# LowVBoard_2_0.net
KiCad netlist of a schematic drawn in EAGLE
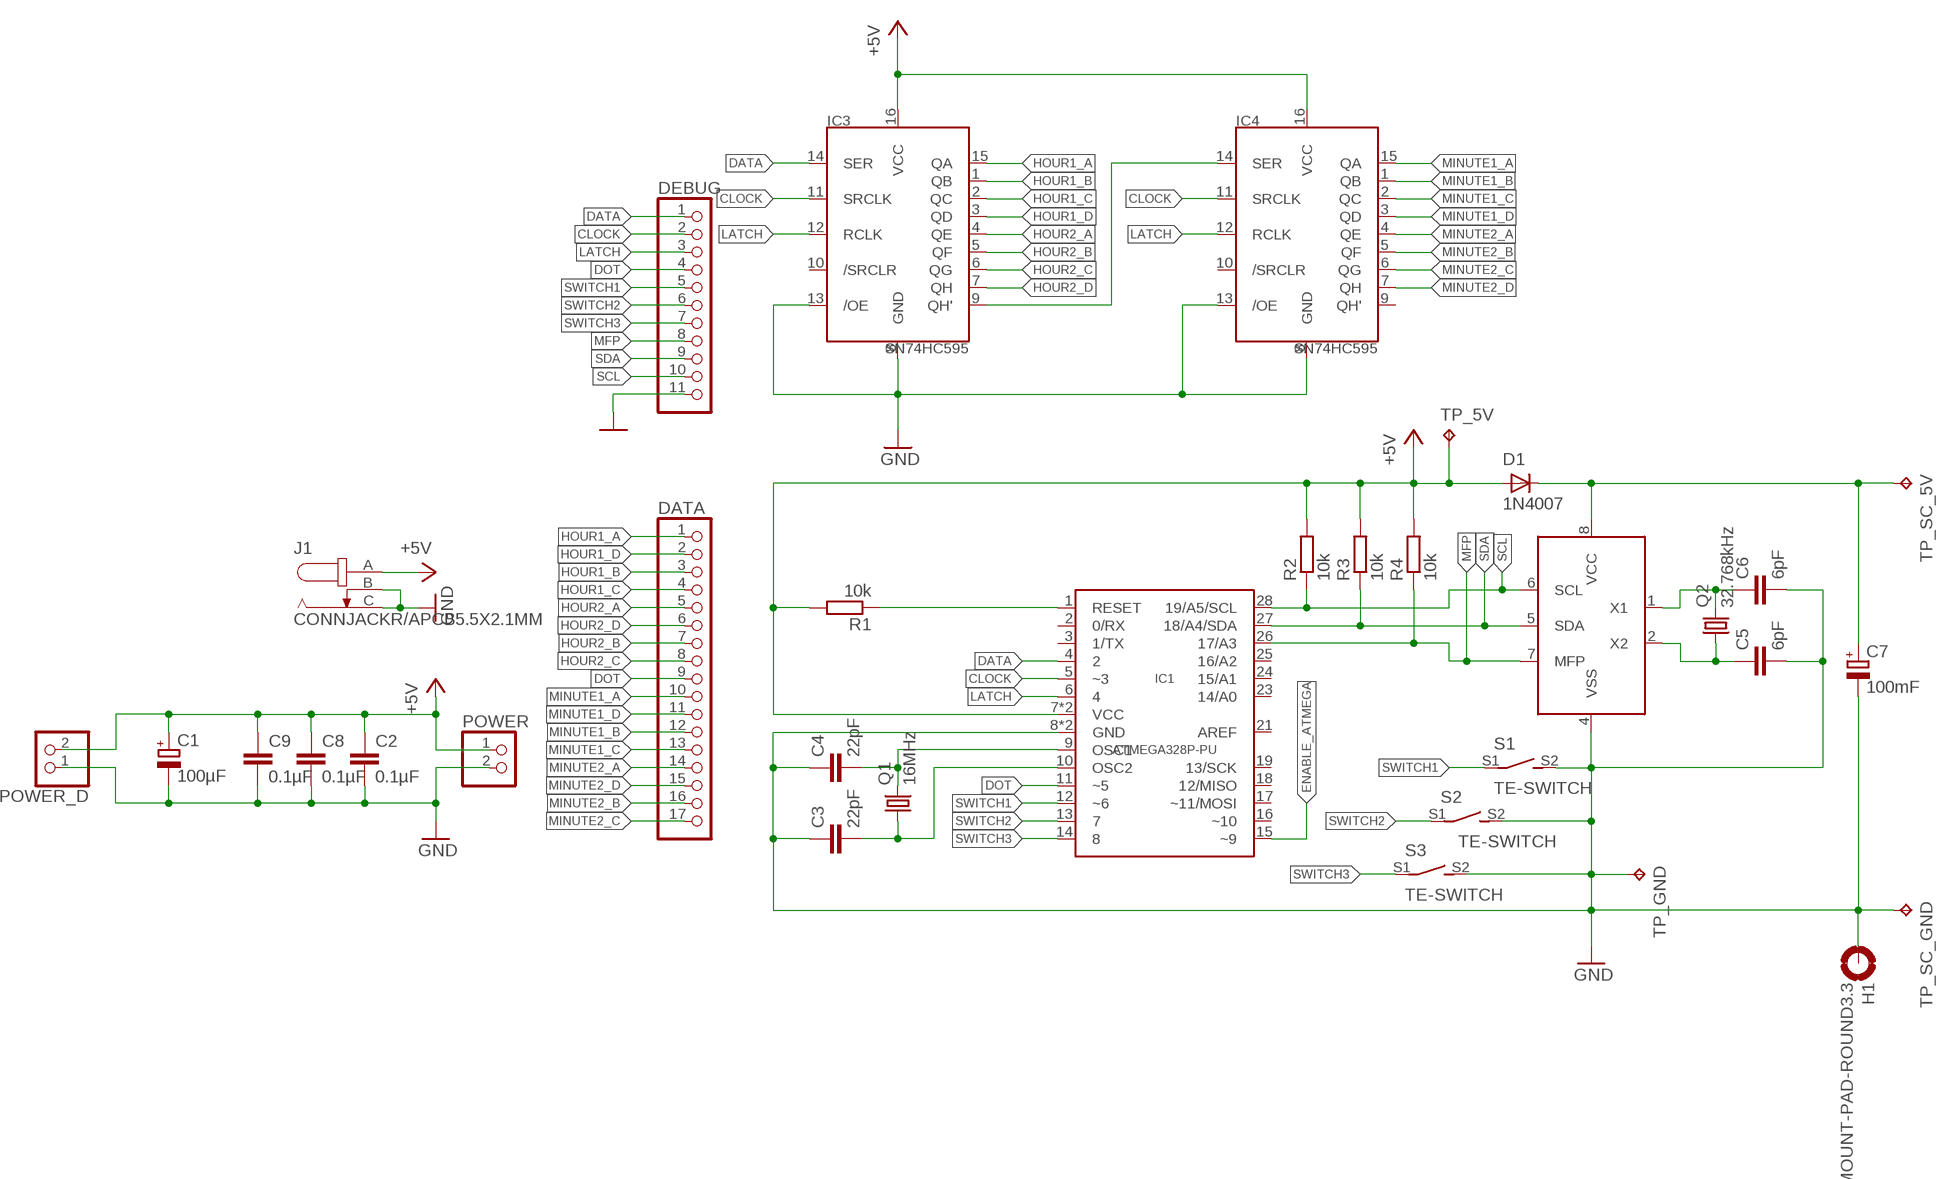
[diagram p0: schematic, sheet 1]

(export (version "E")
  (design (tool "Eeschema 10.0.6"))
  (components
    (comp (ref "C1")
      (value "100µF")
      (footprint "eagle-import:E2-5")
      (libsource (lib "eagle-import") (part "CPOL-EUE2-5"))
    )
    (comp (ref "C2")
      (value "0.1µF")
      (footprint "eagle-import:C025-024X044")
      (libsource (lib "eagle-import") (part "C-EU025-024X044"))
    )
    (comp (ref "C3")
      (value "22pF")
      (footprint "eagle-import:C025-024X044")
      (libsource (lib "eagle-import") (part "C-EU025-024X044"))
    )
    (comp (ref "C4")
      (value "22pF")
      (footprint "eagle-import:C025-024X044")
      (libsource (lib "eagle-import") (part "C-EU025-024X044"))
    )
    (comp (ref "C5")
      (value "6pF")
      (footprint "eagle-import:C025-024X044")
      (libsource (lib "eagle-import") (part "C-EU025-024X044"))
    )
    (comp (ref "C6")
      (value "6pF")
      (footprint "eagle-import:C025-024X044")
      (libsource (lib "eagle-import") (part "C-EU025-024X044"))
    )
    (comp (ref "C7")
      (value "100mF")
      (footprint "eagle-import:SUPERCAP-11.5")
      (libsource (lib "eagle-import") (part "FTW0H104ZF"))
    )
    (comp (ref "C8")
      (value "0.1µF")
      (footprint "eagle-import:C025-024X044")
      (libsource (lib "eagle-import") (part "C-EU025-024X044"))
    )
    (comp (ref "C9")
      (value "0.1µF")
      (footprint "eagle-import:C025-024X044")
      (libsource (lib "eagle-import") (part "C-EU025-024X044"))
    )
    (comp (ref "D1")
      (value "1N4007")
      (footprint "eagle-import:DO41-7.6")
      (libsource (lib "eagle-import") (part "1N4007"))
    )
    (comp (ref "DATA")
      (value "PINHD-1X17")
      (footprint "eagle-import:1X17")
      (libsource (lib "eagle-import") (part "PINHD-1X17"))
    )
    (comp (ref "DEBUG")
      (value "PINHD-1X11/90")
      (footprint "eagle-import:1X11_90")
      (libsource (lib "eagle-import") (part "PINHD-1X11/90"))
    )
    (comp (ref "H1")
      (value "MOUNT-PAD-ROUND3.3")
      (footprint "eagle-import:3,3-PAD")
      (libsource (lib "eagle-import") (part "MOUNT-PAD-ROUND3.3"))
    )
    (comp (ref "IC1")
      (value "ATMEGA328P-PU")
      (footprint "eagle-import:DIP28")
      (libsource (lib "eagle-import") (part "ATMEGA328P-PU"))
    )
    (comp (ref "IC2")
      (value "MCP7940M")
      (footprint "eagle-import:DIL8")
      (libsource (lib "eagle-import") (part "MCP7940M-I/P"))
    )
    (comp (ref "IC3")
      (value "SN74HC595")
      (footprint "eagle-import:DIL16")
      (libsource (lib "eagle-import") (part "SN74HC595"))
    )
    (comp (ref "IC4")
      (value "SN74HC595")
      (footprint "eagle-import:DIL16")
      (libsource (lib "eagle-import") (part "SN74HC595"))
    )
    (comp (ref "J1")
      (value "CONNJACKR/APCB5.5X2.1MM")
      (footprint "eagle-import:CONNJACKR_APCB5.5X2.1MM")
      (libsource (lib "eagle-import") (part "CONNJACKR/APCB5.5X2.1MM"))
    )
    (comp (ref "POWER")
      (value "PINHD-1X2")
      (footprint "eagle-import:1X02")
      (libsource (lib "eagle-import") (part "PINHD-1X2"))
    )
    (comp (ref "POWER_D")
      (value "PINHD-1X2/90")
      (footprint "eagle-import:1X02_90")
      (libsource (lib "eagle-import") (part "PINHD-1X2/90"))
    )
    (comp (ref "Q1")
      (value "16MHz")
      (footprint "eagle-import:HC49_S")
      (libsource (lib "eagle-import") (part "CRYSTALHC49S"))
    )
    (comp (ref "Q2")
      (value "32.768kHz")
      (footprint "eagle-import:CFS-206")
      (libsource (lib "eagle-import") (part "CFS-206"))
    )
    (comp (ref "R1")
      (value "10k")
      (footprint "eagle-import:0207_7")
      (libsource (lib "eagle-import") (part "R-EU_0207/7"))
    )
    (comp (ref "R2")
      (value "10k")
      (footprint "eagle-import:0207_7")
      (libsource (lib "eagle-import") (part "R-EU_0207/7"))
    )
    (comp (ref "R3")
      (value "10k")
      (footprint "eagle-import:0207_7")
      (libsource (lib "eagle-import") (part "R-EU_0207/7"))
    )
    (comp (ref "R4")
      (value "10k")
      (footprint "eagle-import:0207_7")
      (libsource (lib "eagle-import") (part "R-EU_0207/7"))
    )
    (comp (ref "S1")
      (value "TE-SWITCH")
      (footprint "eagle-import:TE-SWITCH")
      (libsource (lib "eagle-import") (part "TE-SWITCH"))
    )
    (comp (ref "S2")
      (value "TE-SWITCH")
      (footprint "eagle-import:TE-SWITCH")
      (libsource (lib "eagle-import") (part "TE-SWITCH"))
    )
    (comp (ref "S3")
      (value "TE-SWITCH")
      (footprint "eagle-import:TE-SWITCH")
      (libsource (lib "eagle-import") (part "TE-SWITCH"))
    )
    (comp (ref "TP_5V")
      (value "TPPAD1-13")
      (footprint "eagle-import:P1-13")
      (libsource (lib "eagle-import") (part "TPPAD1-13"))
    )
    (comp (ref "TP_GND")
      (value "TPPAD1-13")
      (footprint "eagle-import:P1-13")
      (libsource (lib "eagle-import") (part "TPPAD1-13"))
    )
    (comp (ref "TP_SC_5V")
      (value "TPPAD1-13")
      (footprint "eagle-import:P1-13")
      (libsource (lib "eagle-import") (part "TPPAD1-13"))
    )
    (comp (ref "TP_SC_GND")
      (value "TPPAD1-13")
      (footprint "eagle-import:P1-13")
      (libsource (lib "eagle-import") (part "TPPAD1-13"))
    )
  )
  (nets
    (net (code "1") (name "+5V") (class "Default")
      (node (ref "C1") (pin "+") (pinfunction "+_+") (pintype "passive"))
      (node (ref "C2") (pin "1") (pinfunction "1_1") (pintype "passive"))
      (node (ref "C8") (pin "1") (pinfunction "1_1") (pintype "passive"))
      (node (ref "C9") (pin "1") (pinfunction "1_1") (pintype "passive"))
      (node (ref "D1") (pin "A") (pinfunction "A_A") (pintype "passive"))
      (node (ref "IC1") (pin "20") (pinfunction "VCC_20") (pintype "bidirectional"))
      (node (ref "IC1") (pin "7") (pinfunction "VCC_7") (pintype "bidirectional"))
      (node (ref "IC3") (pin "16") (pinfunction "VCC_16") (pintype "bidirectional"))
      (node (ref "IC4") (pin "16") (pinfunction "VCC_16") (pintype "bidirectional"))
      (node (ref "J1") (pin "A") (pinfunction "A_A") (pintype "passive"))
      (node (ref "POWER") (pin "1") (pinfunction "1_1") (pintype "passive"))
      (node (ref "POWER_D") (pin "2") (pinfunction "2_2") (pintype "passive"))
      (node (ref "R1") (pin "2") (pinfunction "2_2") (pintype "passive"))
      (node (ref "R2") (pin "2") (pinfunction "2_2") (pintype "passive"))
      (node (ref "R3") (pin "2") (pinfunction "2_2") (pintype "passive"))
      (node (ref "R4") (pin "2") (pinfunction "2_2") (pintype "passive"))
      (node (ref "TP_5V") (pin "TP") (pinfunction "TP_TP") (pintype "input"))
    )
    (net (code "2") (name "CLOCK") (class "Default")
      (node (ref "DEBUG") (pin "2") (pinfunction "2_2") (pintype "passive"))
      (node (ref "IC1") (pin "5") (pinfunction "~{3}_5") (pintype "bidirectional"))
      (node (ref "IC3") (pin "11") (pinfunction "SRCLK_11") (pintype "bidirectional"))
      (node (ref "IC4") (pin "11") (pinfunction "SRCLK_11") (pintype "bidirectional"))
    )
    (net (code "3") (name "DATA") (class "Default")
      (node (ref "DEBUG") (pin "1") (pinfunction "1_1") (pintype "passive"))
      (node (ref "IC1") (pin "4") (pinfunction "2_4") (pintype "bidirectional"))
      (node (ref "IC3") (pin "14") (pinfunction "SER_14") (pintype "bidirectional"))
    )
    (net (code "4") (name "DOT") (class "Default")
      (node (ref "DATA") (pin "9") (pinfunction "9_9") (pintype "passive"))
      (node (ref "DEBUG") (pin "4") (pinfunction "4_4") (pintype "passive"))
      (node (ref "IC1") (pin "11") (pinfunction "~{5}_11") (pintype "bidirectional"))
    )
    (net (code "5") (name "ENABLE_ATMEGA") (class "Default")
      (node (ref "IC1") (pin "15") (pinfunction "~{9}_15") (pintype "bidirectional"))
    )
    (net (code "6") (name "GND") (class "Default")
      (node (ref "C1") (pin "-") (pinfunction "-_-") (pintype "passive"))
      (node (ref "C2") (pin "2") (pinfunction "2_2") (pintype "passive"))
      (node (ref "C3") (pin "1") (pinfunction "1_1") (pintype "passive"))
      (node (ref "C4") (pin "1") (pinfunction "1_1") (pintype "passive"))
      (node (ref "C5") (pin "2") (pinfunction "2_2") (pintype "passive"))
      (node (ref "C6") (pin "2") (pinfunction "2_2") (pintype "passive"))
      (node (ref "C7") (pin "-") (pinfunction "-_-") (pintype "passive"))
      (node (ref "C8") (pin "2") (pinfunction "2_2") (pintype "passive"))
      (node (ref "C9") (pin "2") (pinfunction "2_2") (pintype "passive"))
      (node (ref "DEBUG") (pin "11") (pinfunction "11_11") (pintype "passive"))
      (node (ref "H1") (pin "B3,3") (pinfunction "MOUNT_B3,3") (pintype "passive"))
      (node (ref "IC1") (pin "22") (pinfunction "GND_22") (pintype "bidirectional"))
      (node (ref "IC1") (pin "8") (pinfunction "GND_8") (pintype "bidirectional"))
      (node (ref "IC2") (pin "4") (pinfunction "VSS_4") (pintype "bidirectional"))
      (node (ref "IC3") (pin "13") (pinfunction "/OE_13") (pintype "bidirectional"))
      (node (ref "IC3") (pin "8") (pinfunction "GND_8") (pintype "bidirectional"))
      (node (ref "IC4") (pin "13") (pinfunction "/OE_13") (pintype "bidirectional"))
      (node (ref "IC4") (pin "8") (pinfunction "GND_8") (pintype "bidirectional"))
      (node (ref "J1") (pin "B") (pinfunction "B_B") (pintype "passive"))
      (node (ref "J1") (pin "C") (pinfunction "C_C") (pintype "passive"))
      (node (ref "POWER") (pin "2") (pinfunction "2_2") (pintype "passive"))
      (node (ref "POWER_D") (pin "1") (pinfunction "1_1") (pintype "passive"))
      (node (ref "S1") (pin "S2") (pinfunction "S_S2") (pintype "passive"))
      (node (ref "S2") (pin "S2") (pinfunction "S_S2") (pintype "passive"))
      (node (ref "S3") (pin "S2") (pinfunction "S_S2") (pintype "passive"))
      (node (ref "TP_GND") (pin "TP") (pinfunction "TP_TP") (pintype "input"))
      (node (ref "TP_SC_GND") (pin "TP") (pinfunction "TP_TP") (pintype "input"))
    )
    (net (code "7") (name "HOUR1_A") (class "Default")
      (node (ref "DATA") (pin "1") (pinfunction "1_1") (pintype "passive"))
      (node (ref "IC3") (pin "15") (pinfunction "QA_15") (pintype "bidirectional"))
    )
    (net (code "8") (name "HOUR1_B") (class "Default")
      (node (ref "DATA") (pin "3") (pinfunction "3_3") (pintype "passive"))
      (node (ref "IC3") (pin "1") (pinfunction "QB_1") (pintype "bidirectional"))
    )
    (net (code "9") (name "HOUR1_C") (class "Default")
      (node (ref "DATA") (pin "4") (pinfunction "4_4") (pintype "passive"))
      (node (ref "IC3") (pin "2") (pinfunction "QC_2") (pintype "bidirectional"))
    )
    (net (code "10") (name "HOUR1_D") (class "Default")
      (node (ref "DATA") (pin "2") (pinfunction "2_2") (pintype "passive"))
      (node (ref "IC3") (pin "3") (pinfunction "QD_3") (pintype "bidirectional"))
    )
    (net (code "11") (name "HOUR2_A") (class "Default")
      (node (ref "DATA") (pin "5") (pinfunction "5_5") (pintype "passive"))
      (node (ref "IC3") (pin "4") (pinfunction "QE_4") (pintype "bidirectional"))
    )
    (net (code "12") (name "HOUR2_B") (class "Default")
      (node (ref "DATA") (pin "7") (pinfunction "7_7") (pintype "passive"))
      (node (ref "IC3") (pin "5") (pinfunction "QF_5") (pintype "bidirectional"))
    )
    (net (code "13") (name "HOUR2_C") (class "Default")
      (node (ref "DATA") (pin "8") (pinfunction "8_8") (pintype "passive"))
      (node (ref "IC3") (pin "6") (pinfunction "QG_6") (pintype "bidirectional"))
    )
    (net (code "14") (name "HOUR2_D") (class "Default")
      (node (ref "DATA") (pin "6") (pinfunction "6_6") (pintype "passive"))
      (node (ref "IC3") (pin "7") (pinfunction "QH_7") (pintype "bidirectional"))
    )
    (net (code "15") (name "LATCH") (class "Default")
      (node (ref "DEBUG") (pin "3") (pinfunction "3_3") (pintype "passive"))
      (node (ref "IC1") (pin "6") (pinfunction "4_6") (pintype "bidirectional"))
      (node (ref "IC3") (pin "12") (pinfunction "RCLK_12") (pintype "bidirectional"))
      (node (ref "IC4") (pin "12") (pinfunction "RCLK_12") (pintype "bidirectional"))
    )
    (net (code "16") (name "MFP") (class "Default")
      (node (ref "DEBUG") (pin "8") (pinfunction "8_8") (pintype "passive"))
      (node (ref "IC1") (pin "26") (pinfunction "17/A3_26") (pintype "bidirectional"))
      (node (ref "IC2") (pin "7") (pinfunction "MFP_7") (pintype "bidirectional"))
      (node (ref "R4") (pin "1") (pinfunction "1_1") (pintype "passive"))
    )
    (net (code "17") (name "MINUTE1_A") (class "Default")
      (node (ref "DATA") (pin "10") (pinfunction "10_10") (pintype "passive"))
      (node (ref "IC4") (pin "15") (pinfunction "QA_15") (pintype "bidirectional"))
    )
    (net (code "18") (name "MINUTE1_B") (class "Default")
      (node (ref "DATA") (pin "12") (pinfunction "12_12") (pintype "passive"))
      (node (ref "IC4") (pin "1") (pinfunction "QB_1") (pintype "bidirectional"))
    )
    (net (code "19") (name "MINUTE1_C") (class "Default")
      (node (ref "DATA") (pin "13") (pinfunction "13_13") (pintype "passive"))
      (node (ref "IC4") (pin "2") (pinfunction "QC_2") (pintype "bidirectional"))
    )
    (net (code "20") (name "MINUTE1_D") (class "Default")
      (node (ref "DATA") (pin "11") (pinfunction "11_11") (pintype "passive"))
      (node (ref "IC4") (pin "3") (pinfunction "QD_3") (pintype "bidirectional"))
    )
    (net (code "21") (name "MINUTE2_A") (class "Default")
      (node (ref "DATA") (pin "14") (pinfunction "14_14") (pintype "passive"))
      (node (ref "IC4") (pin "4") (pinfunction "QE_4") (pintype "bidirectional"))
    )
    (net (code "22") (name "MINUTE2_B") (class "Default")
      (node (ref "DATA") (pin "16") (pinfunction "16_16") (pintype "passive"))
      (node (ref "IC4") (pin "5") (pinfunction "QF_5") (pintype "bidirectional"))
    )
    (net (code "23") (name "MINUTE2_C") (class "Default")
      (node (ref "DATA") (pin "17") (pinfunction "17_17") (pintype "passive"))
      (node (ref "IC4") (pin "6") (pinfunction "QG_6") (pintype "bidirectional"))
    )
    (net (code "24") (name "MINUTE2_D") (class "Default")
      (node (ref "DATA") (pin "15") (pinfunction "15_15") (pintype "passive"))
      (node (ref "IC4") (pin "7") (pinfunction "QH_7") (pintype "bidirectional"))
    )
    (net (code "25") (name "Net-(IC1-OSC1)") (class "Default")
      (node (ref "C4") (pin "2") (pinfunction "2_2") (pintype "passive"))
      (node (ref "IC1") (pin "9") (pinfunction "OSC1_9") (pintype "bidirectional"))
      (node (ref "Q1") (pin "2") (pinfunction "2_2") (pintype "passive"))
    )
    (net (code "26") (name "Net-(IC1-OSC2)") (class "Default")
      (node (ref "C3") (pin "2") (pinfunction "2_2") (pintype "passive"))
      (node (ref "IC1") (pin "10") (pinfunction "OSC2_10") (pintype "bidirectional"))
      (node (ref "Q1") (pin "1") (pinfunction "1_1") (pintype "passive"))
    )
    (net (code "27") (name "Net-(IC1-RESET)") (class "Default")
      (node (ref "IC1") (pin "1") (pinfunction "RESET_1") (pintype "bidirectional"))
      (node (ref "R1") (pin "1") (pinfunction "1_1") (pintype "passive"))
    )
    (net (code "28") (name "Net-(IC2-VCC)") (class "Default")
      (node (ref "C7") (pin "+") (pinfunction "+_+") (pintype "passive"))
      (node (ref "D1") (pin "C") (pinfunction "C_C") (pintype "passive"))
      (node (ref "IC2") (pin "8") (pinfunction "VCC_8") (pintype "bidirectional"))
      (node (ref "TP_SC_5V") (pin "TP") (pinfunction "TP_TP") (pintype "input"))
    )
    (net (code "29") (name "Net-(IC2-X1)") (class "Default")
      (node (ref "C6") (pin "1") (pinfunction "1_1") (pintype "passive"))
      (node (ref "IC2") (pin "1") (pinfunction "X1_1") (pintype "bidirectional"))
      (node (ref "Q2") (pin "P$2") (pinfunction "2_P$2") (pintype "passive"))
    )
    (net (code "30") (name "Net-(IC2-X2)") (class "Default")
      (node (ref "C5") (pin "1") (pinfunction "1_1") (pintype "passive"))
      (node (ref "IC2") (pin "2") (pinfunction "X2_2") (pintype "bidirectional"))
      (node (ref "Q2") (pin "P$1") (pinfunction "1_P$1") (pintype "passive"))
    )
    (net (code "31") (name "Net-(IC3-QH')") (class "Default")
      (node (ref "IC3") (pin "9") (pinfunction "QH'_9") (pintype "bidirectional"))
      (node (ref "IC4") (pin "14") (pinfunction "SER_14") (pintype "bidirectional"))
    )
    (net (code "32") (name "SCL") (class "Default")
      (node (ref "DEBUG") (pin "10") (pinfunction "10_10") (pintype "passive"))
      (node (ref "IC1") (pin "28") (pinfunction "19/A5/SCL_28") (pintype "bidirectional"))
      (node (ref "IC2") (pin "6") (pinfunction "SCL_6") (pintype "bidirectional"))
      (node (ref "R2") (pin "1") (pinfunction "1_1") (pintype "passive"))
    )
    (net (code "33") (name "SDA") (class "Default")
      (node (ref "DEBUG") (pin "9") (pinfunction "9_9") (pintype "passive"))
      (node (ref "IC1") (pin "27") (pinfunction "18/A4/SDA_27") (pintype "bidirectional"))
      (node (ref "IC2") (pin "5") (pinfunction "SDA_5") (pintype "bidirectional"))
      (node (ref "R3") (pin "1") (pinfunction "1_1") (pintype "passive"))
    )
    (net (code "34") (name "SWITCH1") (class "Default")
      (node (ref "DEBUG") (pin "5") (pinfunction "5_5") (pintype "passive"))
      (node (ref "IC1") (pin "12") (pinfunction "~{6}_12") (pintype "bidirectional"))
      (node (ref "S1") (pin "S1") (pinfunction "P_S1") (pintype "passive"))
    )
    (net (code "35") (name "SWITCH2") (class "Default")
      (node (ref "DEBUG") (pin "6") (pinfunction "6_6") (pintype "passive"))
      (node (ref "IC1") (pin "13") (pinfunction "7_13") (pintype "bidirectional"))
      (node (ref "S2") (pin "S1") (pinfunction "P_S1") (pintype "passive"))
    )
    (net (code "36") (name "SWITCH3") (class "Default")
      (node (ref "DEBUG") (pin "7") (pinfunction "7_7") (pintype "passive"))
      (node (ref "IC1") (pin "14") (pinfunction "8_14") (pintype "bidirectional"))
      (node (ref "S3") (pin "S1") (pinfunction "P_S1") (pintype "passive"))
    )
    (net (code "37") (name "unconnected-(IC1-0{slash}RX-Pad2)") (class "Default")
      (node (ref "IC1") (pin "2") (pinfunction "0/RX_2") (pintype "bidirectional"))
    )
    (net (code "38") (name "unconnected-(IC1-1{slash}TX-Pad3)") (class "Default")
      (node (ref "IC1") (pin "3") (pinfunction "1/TX_3") (pintype "bidirectional"))
    )
    (net (code "39") (name "unconnected-(IC1-12{slash}MISO-Pad18)") (class "Default")
      (node (ref "IC1") (pin "18") (pinfunction "12/MISO_18") (pintype "bidirectional"))
    )
    (net (code "40") (name "unconnected-(IC1-13{slash}SCK-Pad19)") (class "Default")
      (node (ref "IC1") (pin "19") (pinfunction "13/SCK_19") (pintype "bidirectional"))
    )
    (net (code "41") (name "unconnected-(IC1-14{slash}A0-Pad23)") (class "Default")
      (node (ref "IC1") (pin "23") (pinfunction "14/A0_23") (pintype "bidirectional"))
    )
    (net (code "42") (name "unconnected-(IC1-15{slash}A1-Pad24)") (class "Default")
      (node (ref "IC1") (pin "24") (pinfunction "15/A1_24") (pintype "bidirectional"))
    )
    (net (code "43") (name "unconnected-(IC1-16{slash}A2-Pad25)") (class "Default")
      (node (ref "IC1") (pin "25") (pinfunction "16/A2_25") (pintype "bidirectional"))
    )
    (net (code "44") (name "unconnected-(IC1-AREF-Pad21)") (class "Default")
      (node (ref "IC1") (pin "21") (pinfunction "AREF_21") (pintype "bidirectional"))
    )
    (net (code "45") (name "unconnected-(IC1-~{10}-Pad16)") (class "Default")
      (node (ref "IC1") (pin "16") (pinfunction "~{10}_16") (pintype "bidirectional"))
    )
    (net (code "46") (name "unconnected-(IC1-~{11{slash}MOSI}-Pad17)") (class "Default")
      (node (ref "IC1") (pin "17") (pinfunction "~{11/MOSI}_17") (pintype "bidirectional"))
    )
    (net (code "47") (name "unconnected-(IC3-{slash}SRCLR-Pad10)") (class "Default")
      (node (ref "IC3") (pin "10") (pinfunction "/SRCLR_10") (pintype "bidirectional"))
    )
    (net (code "48") (name "unconnected-(IC4-QH'-Pad9)") (class "Default")
      (node (ref "IC4") (pin "9") (pinfunction "QH'_9") (pintype "bidirectional"))
    )
    (net (code "49") (name "unconnected-(IC4-{slash}SRCLR-Pad10)") (class "Default")
      (node (ref "IC4") (pin "10") (pinfunction "/SRCLR_10") (pintype "bidirectional"))
    )
  )
)
